# SchematicPorts.net
KiCad netlist of a schematic drawn in Altium Designer
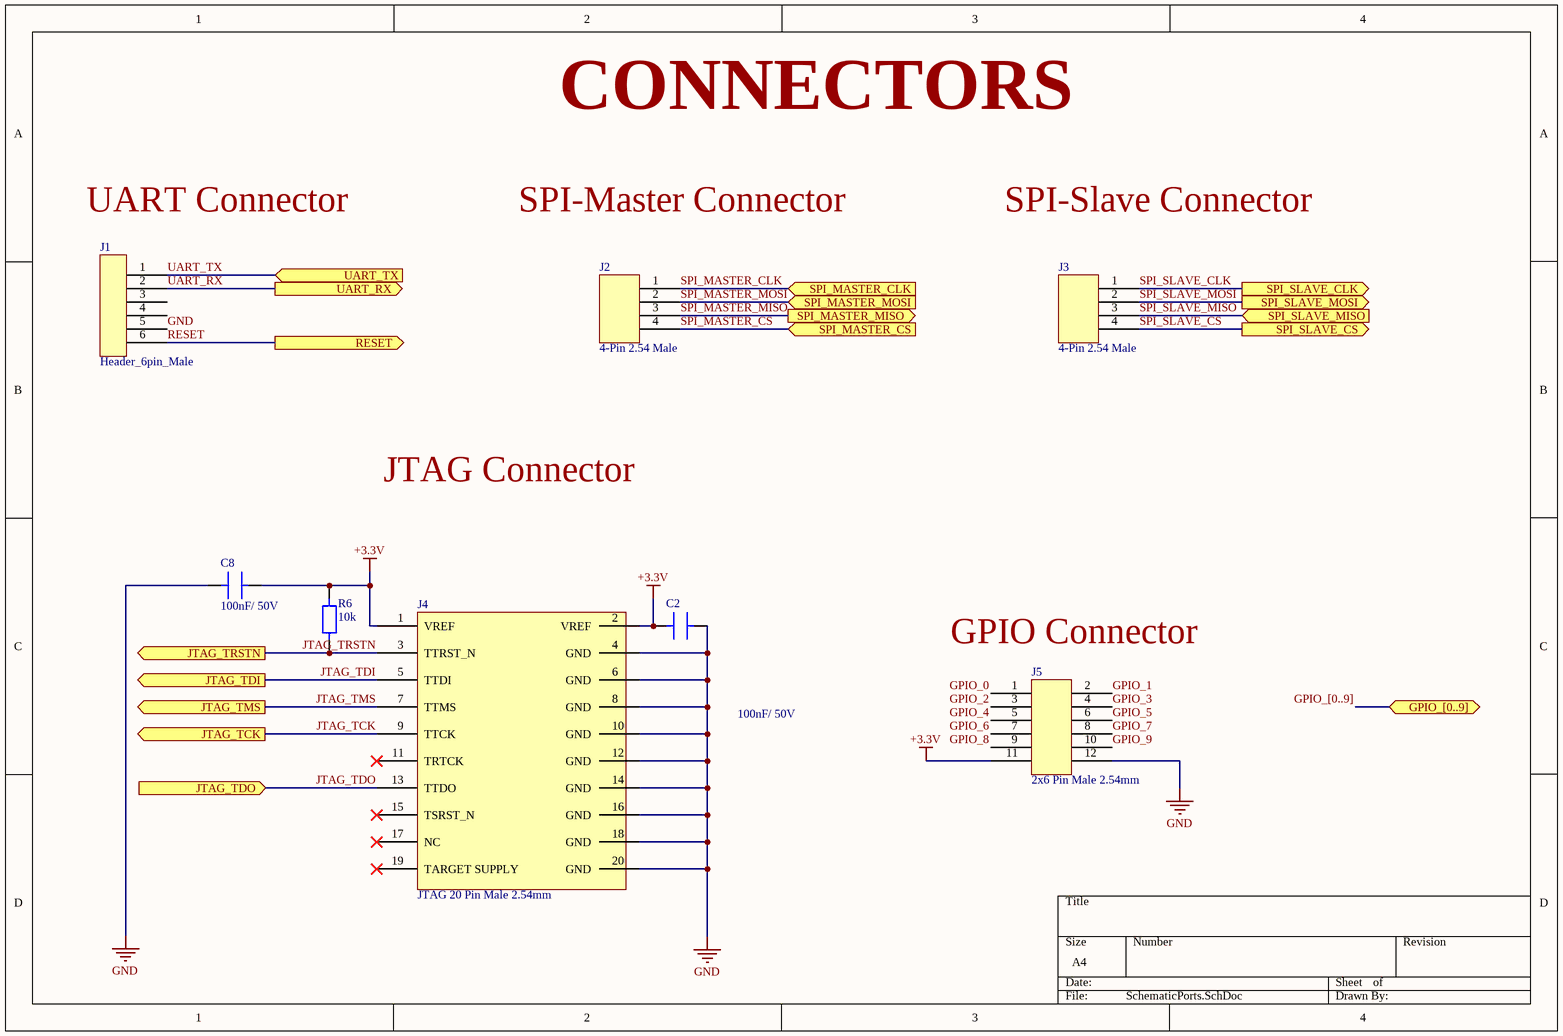
[diagram p0: SchematicPorts.SchDoc]

(export (version "E")
  (design (tool "Eeschema 10.0.6"))
  (components
    (comp (ref "C2")
      (value "100nF/ 50V")
      (footprint "C0603")
      (description "C0603/C0805")
      (libsource (lib "upbracing_library") (part "C 100nF/ 50V"))
    )
    (comp (ref "C8")
      (value "100nF/ 50V")
      (footprint "C0603")
      (description "C0603/C0805")
      (libsource (lib "upbracing_library") (part "C 100nF/ 50V"))
    )
    (comp (ref "J1")
      (value "Header_6pin_Male")
      (footprint "Header_6pin_male")
      (libsource (lib "upbracing_library") (part "Header_6pin_Male"))
    )
    (comp (ref "J2")
      (value "4-Pin 2.54 Male")
      (footprint "DIP4 4X1 Pitch 2.54mm")
      (libsource (lib "upbracing_library") (part "Molex 90120-0124 1x4 Pin Male 2.54mm"))
    )
    (comp (ref "J3")
      (value "4-Pin 2.54 Male")
      (footprint "DIP4 4X1 Pitch 2.54mm")
      (libsource (lib "upbracing_library") (part "Molex 90120-0124 1x4 Pin Male 2.54mm"))
    )
    (comp (ref "J4")
      (value "JTAG 20 Pin Male 2.54mm")
      (footprint "JTAG 20-Pin")
      (libsource (lib "upbracing_library") (part "JTAG 20-Pin 2.54 ARM USB-Tiny H"))
    )
    (comp (ref "J5")
      (value "2x6 Pin Male 2.54mm")
      (footprint "DIP12 2X6 Pitch 2.54mm")
      (libsource (lib "upbracing_library") (part "Molex 90131-1086 2x6 PIn Header_1"))
    )
    (comp (ref "R6")
      (value "10k")
      (footprint "R0603")
      (description "0805")
      (libsource (lib "upbracing_library") (part "RES_10k"))
    )
  )
  (nets
    (net (code "1") (name "+3.3V") (class "Default")
      (node (ref "C2") (pin "2") (pinfunction "2_2") (pintype "passive"))
      (node (ref "C8") (pin "1") (pinfunction "1_1") (pintype "passive"))
      (node (ref "J4") (pin "1") (pinfunction "VREF_1") (pintype "passive"))
      (node (ref "J4") (pin "2") (pinfunction "VREF_2") (pintype "passive"))
      (node (ref "J5") (pin "11") (pinfunction "11_11") (pintype "passive"))
      (node (ref "R6") (pin "2") (pinfunction "2_2") (pintype "passive"))
    )
    (net (code "2") (name "/GPIO_0") (class "Default")
      (node (ref "J5") (pin "1") (pinfunction "1_1") (pintype "passive"))
    )
    (net (code "3") (name "/GPIO_1") (class "Default")
      (node (ref "J5") (pin "2") (pinfunction "2_2") (pintype "passive"))
    )
    (net (code "4") (name "/GPIO_2") (class "Default")
      (node (ref "J5") (pin "3") (pinfunction "3_3") (pintype "passive"))
    )
    (net (code "5") (name "/GPIO_3") (class "Default")
      (node (ref "J5") (pin "4") (pinfunction "4_4") (pintype "passive"))
    )
    (net (code "6") (name "/GPIO_4") (class "Default")
      (node (ref "J5") (pin "5") (pinfunction "5_5") (pintype "passive"))
    )
    (net (code "7") (name "/GPIO_5") (class "Default")
      (node (ref "J5") (pin "6") (pinfunction "6_6") (pintype "passive"))
    )
    (net (code "8") (name "/GPIO_6") (class "Default")
      (node (ref "J5") (pin "7") (pinfunction "7_7") (pintype "passive"))
    )
    (net (code "9") (name "/GPIO_7") (class "Default")
      (node (ref "J5") (pin "8") (pinfunction "8_8") (pintype "passive"))
    )
    (net (code "10") (name "/GPIO_8") (class "Default")
      (node (ref "J5") (pin "9") (pinfunction "9_9") (pintype "passive"))
    )
    (net (code "11") (name "/GPIO_9") (class "Default")
      (node (ref "J5") (pin "10") (pinfunction "10_10") (pintype "passive"))
    )
    (net (code "13") (name "/JTAG_TCK") (class "Default")
      (node (ref "J4") (pin "9") (pinfunction "TTCK_9") (pintype "passive"))
    )
    (net (code "14") (name "/JTAG_TDI") (class "Default")
      (node (ref "J4") (pin "5") (pinfunction "TTDI_5") (pintype "passive"))
    )
    (net (code "15") (name "/JTAG_TDO") (class "Default")
      (node (ref "J4") (pin "13") (pinfunction "TTDO_13") (pintype "passive"))
    )
    (net (code "16") (name "/JTAG_TMS") (class "Default")
      (node (ref "J4") (pin "7") (pinfunction "TTMS_7") (pintype "passive"))
    )
    (net (code "17") (name "/JTAG_TRSTN") (class "Default")
      (node (ref "J4") (pin "3") (pinfunction "TTRST_N_3") (pintype "passive"))
      (node (ref "R6") (pin "1") (pinfunction "1_1") (pintype "passive"))
    )
    (net (code "18") (name "/RESET") (class "Default")
      (node (ref "J1") (pin "6") (pinfunction "6_6") (pintype "passive"))
    )
    (net (code "19") (name "/SPI_MASTER_CLK") (class "Default")
      (node (ref "J2") (pin "1") (pinfunction "1_1") (pintype "passive"))
    )
    (net (code "20") (name "/SPI_MASTER_CS") (class "Default")
      (node (ref "J2") (pin "4") (pinfunction "4_4") (pintype "passive"))
    )
    (net (code "21") (name "/SPI_MASTER_MISO") (class "Default")
      (node (ref "J2") (pin "3") (pinfunction "3_3") (pintype "passive"))
    )
    (net (code "22") (name "/SPI_MASTER_MOSI") (class "Default")
      (node (ref "J2") (pin "2") (pinfunction "2_2") (pintype "passive"))
    )
    (net (code "23") (name "/SPI_SLAVE_CLK") (class "Default")
      (node (ref "J3") (pin "1") (pinfunction "1_1") (pintype "passive"))
    )
    (net (code "24") (name "/SPI_SLAVE_CS") (class "Default")
      (node (ref "J3") (pin "4") (pinfunction "4_4") (pintype "passive"))
    )
    (net (code "25") (name "/SPI_SLAVE_MISO") (class "Default")
      (node (ref "J3") (pin "3") (pinfunction "3_3") (pintype "passive"))
    )
    (net (code "26") (name "/SPI_SLAVE_MOSI") (class "Default")
      (node (ref "J3") (pin "2") (pinfunction "2_2") (pintype "passive"))
    )
    (net (code "27") (name "/UART_RX") (class "Default")
      (node (ref "J1") (pin "2") (pinfunction "2_2") (pintype "passive"))
    )
    (net (code "28") (name "/UART_TX") (class "Default")
      (node (ref "J1") (pin "1") (pinfunction "1_1") (pintype "passive"))
    )
    (net (code "29") (name "GND") (class "Default")
      (node (ref "C2") (pin "1") (pinfunction "1_1") (pintype "passive"))
      (node (ref "C8") (pin "2") (pinfunction "2_2") (pintype "passive"))
      (node (ref "J1") (pin "5") (pinfunction "5_5") (pintype "passive"))
      (node (ref "J4") (pin "10") (pinfunction "GND_10") (pintype "passive"))
      (node (ref "J4") (pin "12") (pinfunction "GND_12") (pintype "passive"))
      (node (ref "J4") (pin "14") (pinfunction "GND_14") (pintype "passive"))
      (node (ref "J4") (pin "16") (pinfunction "GND_16") (pintype "passive"))
      (node (ref "J4") (pin "18") (pinfunction "GND_18") (pintype "passive"))
      (node (ref "J4") (pin "20") (pinfunction "GND_20") (pintype "passive"))
      (node (ref "J4") (pin "4") (pinfunction "GND_4") (pintype "passive"))
      (node (ref "J4") (pin "6") (pinfunction "GND_6") (pintype "passive"))
      (node (ref "J4") (pin "8") (pinfunction "GND_8") (pintype "passive"))
      (node (ref "J5") (pin "12") (pinfunction "12_12") (pintype "passive"))
    )
    (net (code "30") (name "unconnected-(J1-Pad3)") (class "Default")
      (node (ref "J1") (pin "3") (pinfunction "3_3") (pintype "passive"))
    )
    (net (code "31") (name "unconnected-(J1-Pad4)") (class "Default")
      (node (ref "J1") (pin "4") (pinfunction "4_4") (pintype "passive"))
    )
    (net (code "32") (name "unconnected-(J4-NC-Pad17)") (class "Default")
      (node (ref "J4") (pin "17") (pinfunction "NC_17") (pintype "passive+no_connect"))
    )
    (net (code "33") (name "unconnected-(J4-TARGET_SUPPLY-Pad19)") (class "Default")
      (node (ref "J4") (pin "19") (pinfunction "TARGET_SUPPLY_19") (pintype "passive+no_connect"))
    )
    (net (code "34") (name "unconnected-(J4-TRTCK-Pad11)") (class "Default")
      (node (ref "J4") (pin "11") (pinfunction "TRTCK_11") (pintype "passive+no_connect"))
    )
    (net (code "35") (name "unconnected-(J4-TSRST_N-Pad15)") (class "Default")
      (node (ref "J4") (pin "15") (pinfunction "TSRST_N_15") (pintype "passive+no_connect"))
    )
  )
)
